# cpu.net
KiCad netlist of a schematic drawn in Altium Designer
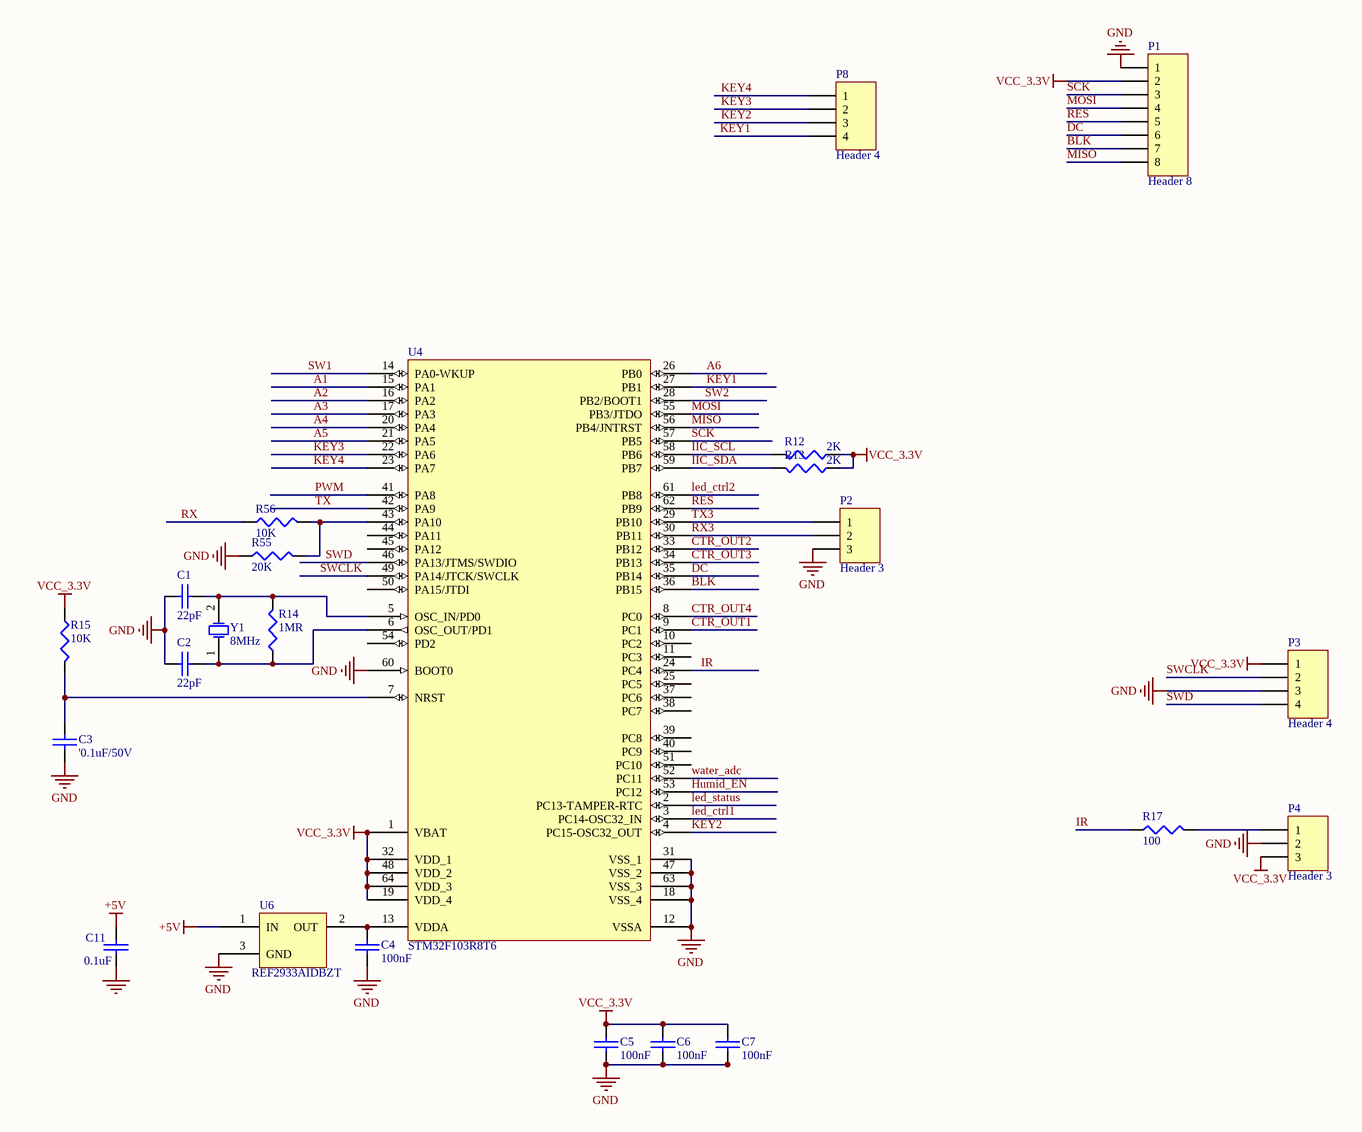
[diagram p0: cpu.SchDoc]

(export (version "E")
  (design (tool "Eeschema 10.0.6"))
  (components
    (comp (ref "C1")
      (value "22pF")
      (footprint "0805c")
      (description "Capacitor")
      (libsource (lib "SM") (part "CAP"))
    )
    (comp (ref "C2")
      (value "22pF")
      (footprint "0805c")
      (description "Capacitor")
      (libsource (lib "SM") (part "CAP"))
    )
    (comp (ref "C3")
      (value "'0.1uF/50V")
      (footprint "0805c")
      (description "Capacitor")
      (libsource (lib "SM") (part "CAP"))
    )
    (comp (ref "C4")
      (value "100nF")
      (footprint "0805c")
      (description "Capacitor")
      (libsource (lib "SM") (part "CAP"))
    )
    (comp (ref "C5")
      (value "100nF")
      (footprint "0805c")
      (description "Capacitor")
      (libsource (lib "SM") (part "CAP"))
    )
    (comp (ref "C6")
      (value "100nF")
      (footprint "0805c")
      (description "Capacitor")
      (libsource (lib "SM") (part "CAP"))
    )
    (comp (ref "C7")
      (value "100nF")
      (footprint "0805c")
      (description "Capacitor")
      (libsource (lib "SM") (part "CAP"))
    )
    (comp (ref "C11")
      (value "0.1uF")
      (footprint "0603C")
      (description "Capacitor")
      (libsource (lib "*") (part "CAP"))
    )
    (comp (ref "P1")
      (value "Header 8")
      (footprint "HDR1X8")
      (description "Header, 8-Pin")
      (fields (field (name "PUBLISHER") "Altium Limited"))
      (libsource (lib "Miscellaneous Connectors") (part "Header 8"))
    )
    (comp (ref "P2")
      (value "Header 3")
      (footprint "HDR1X3")
      (description "Header, 3-Pin")
      (fields (field (name "PUBLISHER") "Altium Limited"))
      (libsource (lib "Miscellaneous Connectors") (part "Header 3"))
    )
    (comp (ref "P3")
      (value "Header 4")
      (footprint "HDR1X4")
      (description "Header, 4-Pin")
      (fields (field (name "PUBLISHER") "Altium Limited"))
      (libsource (lib "Miscellaneous Connectors") (part "Header 4"))
    )
    (comp (ref "P4")
      (value "Header 3")
      (footprint "HDR1X3")
      (description "Header, 3-Pin")
      (fields (field (name "PUBLISHER") "Altium Limited"))
      (libsource (lib "Miscellaneous Connectors") (part "Header 3"))
    )
    (comp (ref "P8")
      (value "Header 4")
      (footprint "HDR1X4")
      (description "Header, 4-Pin")
      (fields (field (name "PUBLISHER") "Altium Limited"))
      (libsource (lib "Miscellaneous Connectors") (part "Header 4"))
    )
    (comp (ref "R12")
      (value "2K")
      (footprint "0805R")
      (description "Resistor")
      (fields (field (name "PUBLISHER") "Altium Limited"))
      (libsource (lib "SM") (part "Res3"))
    )
    (comp (ref "R13")
      (value "2K")
      (footprint "0805R")
      (description "Resistor")
      (fields (field (name "PUBLISHER") "Altium Limited"))
      (libsource (lib "SM") (part "Res3"))
    )
    (comp (ref "R14")
      (value "1MR")
      (footprint "0805R")
      (description "Resistor")
      (fields (field (name "PUBLISHER") "Altium Limited"))
      (libsource (lib "SM") (part "Res3"))
    )
    (comp (ref "R15")
      (value "10K")
      (footprint "0805R")
      (description "Resistor")
      (fields (field (name "PUBLISHER") "Altium Limited"))
      (libsource (lib "SM") (part "Res3"))
    )
    (comp (ref "R17")
      (value "100")
      (footprint "0603R")
      (description "Resistor")
      (fields (field (name "PUBLISHER") "Altium Limited"))
      (libsource (lib "SM") (part "Res3"))
    )
    (comp (ref "R55")
      (value "20K")
      (footprint "0603R")
      (description "Resistor")
      (fields (field (name "PUBLISHER") "Altium Limited"))
      (libsource (lib "SM") (part "Res3"))
    )
    (comp (ref "R56")
      (value "10K")
      (footprint "0805R")
      (description "Resistor")
      (fields (field (name "PUBLISHER") "Altium Limited"))
      (libsource (lib "SM") (part "Res3"))
    )
    (comp (ref "U4")
      (value "STM32F103R8T6")
      (footprint "LQFP-64")
      (description "STM32 ARM-based 32-bit MCU with 64 Kbytes Flash, 64-pin LQFP, Industrial Temperature")
      (fields (field (name "PUBLISHER") "Altium Limited"))
      (libsource (lib "ST Microcontroller 32-Bit STM32") (part "STM32F103R8T6"))
    )
    (comp (ref "U6")
      (value "REF2933AIDBZT")
      (footprint "SOT23-3")
      (libsource (lib "Schlib1") (part "REF3012"))
    )
    (comp (ref "Y1")
      (value "8MHz")
      (footprint "SMT5032")
      (description "Crystal Oscillator")
      (fields (field (name "PUBLISHER") "Altium Limited"))
      (libsource (lib "Miscellaneous Devices") (part "XTAL"))
    )
  )
  (nets
    (net (code "1") (name "+5V") (class "Default")
      (node (ref "C11") (pin "1") (pinfunction "1_1") (pintype "passive"))
      (node (ref "U6") (pin "1") (pinfunction "IN_1") (pintype "passive"))
    )
    (net (code "2") (name "/A1") (class "Default")
      (node (ref "U4") (pin "15") (pinfunction "PA1_15") (pintype "bidirectional"))
    )
    (net (code "3") (name "/A2") (class "Default")
      (node (ref "U4") (pin "16") (pinfunction "PA2_16") (pintype "bidirectional"))
    )
    (net (code "4") (name "/A3") (class "Default")
      (node (ref "U4") (pin "17") (pinfunction "PA3_17") (pintype "bidirectional"))
    )
    (net (code "5") (name "/A4") (class "Default")
      (node (ref "U4") (pin "20") (pinfunction "PA4_20") (pintype "bidirectional"))
    )
    (net (code "6") (name "/A5") (class "Default")
      (node (ref "U4") (pin "21") (pinfunction "PA5_21") (pintype "bidirectional"))
    )
    (net (code "7") (name "/A6") (class "Default")
      (node (ref "U4") (pin "26") (pinfunction "PB0_26") (pintype "bidirectional"))
    )
    (net (code "8") (name "/BLK") (class "Default")
      (node (ref "P1") (pin "7") (pinfunction "7_7") (pintype "passive"))
      (node (ref "U4") (pin "36") (pinfunction "PB15_36") (pintype "bidirectional"))
    )
    (net (code "9") (name "/CTR_OUT1") (class "Default")
      (node (ref "U4") (pin "9") (pinfunction "PC1_9") (pintype "bidirectional"))
    )
    (net (code "10") (name "/CTR_OUT2") (class "Default")
      (node (ref "U4") (pin "33") (pinfunction "PB12_33") (pintype "bidirectional"))
    )
    (net (code "11") (name "/CTR_OUT3") (class "Default")
      (node (ref "U4") (pin "34") (pinfunction "PB13_34") (pintype "bidirectional"))
    )
    (net (code "12") (name "/CTR_OUT4") (class "Default")
      (node (ref "U4") (pin "8") (pinfunction "PC0_8") (pintype "bidirectional"))
    )
    (net (code "13") (name "/DC") (class "Default")
      (node (ref "P1") (pin "6") (pinfunction "6_6") (pintype "passive"))
      (node (ref "U4") (pin "35") (pinfunction "PB14_35") (pintype "bidirectional"))
    )
    (net (code "14") (name "/Humid_EN") (class "Default")
      (node (ref "U4") (pin "53") (pinfunction "PC12_53") (pintype "bidirectional"))
    )
    (net (code "15") (name "/IIC_SCL") (class "Default")
      (node (ref "R12") (pin "2") (pinfunction "2_2") (pintype "passive"))
      (node (ref "U4") (pin "58") (pinfunction "PB6_58") (pintype "bidirectional"))
    )
    (net (code "16") (name "/IIC_SDA") (class "Default")
      (node (ref "R13") (pin "2") (pinfunction "2_2") (pintype "passive"))
      (node (ref "U4") (pin "59") (pinfunction "PB7_59") (pintype "bidirectional"))
    )
    (net (code "17") (name "/IR") (class "Default")
      (node (ref "R17") (pin "1") (pinfunction "1_1") (pintype "passive"))
      (node (ref "U4") (pin "24") (pinfunction "PC4_24") (pintype "bidirectional"))
    )
    (net (code "18") (name "/KEY1") (class "Default")
      (node (ref "P8") (pin "4") (pinfunction "4_4") (pintype "passive"))
      (node (ref "U4") (pin "27") (pinfunction "PB1_27") (pintype "bidirectional"))
    )
    (net (code "19") (name "/KEY2") (class "Default")
      (node (ref "P8") (pin "3") (pinfunction "3_3") (pintype "passive"))
      (node (ref "U4") (pin "4") (pinfunction "PC15-OSC32_OUT_4") (pintype "bidirectional"))
    )
    (net (code "20") (name "/KEY3") (class "Default")
      (node (ref "P8") (pin "2") (pinfunction "2_2") (pintype "passive"))
      (node (ref "U4") (pin "22") (pinfunction "PA6_22") (pintype "bidirectional"))
    )
    (net (code "21") (name "/KEY4") (class "Default")
      (node (ref "P8") (pin "1") (pinfunction "1_1") (pintype "passive"))
      (node (ref "U4") (pin "23") (pinfunction "PA7_23") (pintype "bidirectional"))
    )
    (net (code "22") (name "/MISO") (class "Default")
      (node (ref "P1") (pin "8") (pinfunction "8_8") (pintype "passive"))
      (node (ref "U4") (pin "56") (pinfunction "PB4/JNTRST_56") (pintype "bidirectional"))
    )
    (net (code "23") (name "/MOSI") (class "Default")
      (node (ref "P1") (pin "4") (pinfunction "4_4") (pintype "passive"))
      (node (ref "U4") (pin "55") (pinfunction "PB3/JTDO_55") (pintype "bidirectional"))
    )
    (net (code "24") (name "/PWM") (class "Default")
      (node (ref "U4") (pin "41") (pinfunction "PA8_41") (pintype "bidirectional"))
    )
    (net (code "25") (name "/RES") (class "Default")
      (node (ref "P1") (pin "5") (pinfunction "5_5") (pintype "passive"))
      (node (ref "U4") (pin "62") (pinfunction "PB9_62") (pintype "bidirectional"))
    )
    (net (code "26") (name "/RX") (class "Default")
      (node (ref "R56") (pin "1") (pinfunction "1_1") (pintype "passive"))
    )
    (net (code "27") (name "/RX3") (class "Default")
      (node (ref "P2") (pin "2") (pinfunction "2_2") (pintype "passive"))
      (node (ref "U4") (pin "30") (pinfunction "PB11_30") (pintype "bidirectional"))
    )
    (net (code "28") (name "/SCK") (class "Default")
      (node (ref "P1") (pin "3") (pinfunction "3_3") (pintype "passive"))
      (node (ref "U4") (pin "57") (pinfunction "PB5_57") (pintype "bidirectional"))
    )
    (net (code "29") (name "/SW1") (class "Default")
      (node (ref "U4") (pin "14") (pinfunction "PA0-WKUP_14") (pintype "bidirectional"))
    )
    (net (code "30") (name "/SW2") (class "Default")
      (node (ref "U4") (pin "28") (pinfunction "PB2/BOOT1_28") (pintype "bidirectional"))
    )
    (net (code "31") (name "/SWCLK") (class "Default")
      (node (ref "P3") (pin "2") (pinfunction "2_2") (pintype "passive"))
      (node (ref "U4") (pin "49") (pinfunction "PA14/JTCK/SWCLK_49") (pintype "bidirectional"))
    )
    (net (code "32") (name "/SWD") (class "Default")
      (node (ref "P3") (pin "4") (pinfunction "4_4") (pintype "passive"))
      (node (ref "U4") (pin "46") (pinfunction "PA13/JTMS/SWDIO_46") (pintype "bidirectional"))
    )
    (net (code "33") (name "/TX") (class "Default")
      (node (ref "U4") (pin "42") (pinfunction "PA9_42") (pintype "bidirectional"))
    )
    (net (code "34") (name "/TX3") (class "Default")
      (node (ref "P2") (pin "1") (pinfunction "1_1") (pintype "passive"))
      (node (ref "U4") (pin "29") (pinfunction "PB10_29") (pintype "bidirectional"))
    )
    (net (code "35") (name "/led_ctrl1") (class "Default")
      (node (ref "U4") (pin "3") (pinfunction "PC14-OSC32_IN_3") (pintype "bidirectional"))
    )
    (net (code "36") (name "/led_ctrl2") (class "Default")
      (node (ref "U4") (pin "61") (pinfunction "PB8_61") (pintype "bidirectional"))
    )
    (net (code "37") (name "/led_status") (class "Default")
      (node (ref "U4") (pin "2") (pinfunction "PC13-TAMPER-RTC_2") (pintype "bidirectional"))
    )
    (net (code "38") (name "/water_adc") (class "Default")
      (node (ref "U4") (pin "52") (pinfunction "PC11_52") (pintype "bidirectional"))
    )
    (net (code "39") (name "GND") (class "Default")
      (node (ref "C1") (pin "1") (pinfunction "1_1") (pintype "passive"))
      (node (ref "C11") (pin "2") (pinfunction "2_2") (pintype "passive"))
      (node (ref "C2") (pin "1") (pinfunction "1_1") (pintype "passive"))
      (node (ref "C3") (pin "1") (pinfunction "1_1") (pintype "passive"))
      (node (ref "C4") (pin "1") (pinfunction "1_1") (pintype "passive"))
      (node (ref "C5") (pin "1") (pinfunction "1_1") (pintype "passive"))
      (node (ref "C6") (pin "1") (pinfunction "1_1") (pintype "passive"))
      (node (ref "C7") (pin "1") (pinfunction "1_1") (pintype "passive"))
      (node (ref "P1") (pin "1") (pinfunction "1_1") (pintype "passive"))
      (node (ref "P2") (pin "3") (pinfunction "3_3") (pintype "passive"))
      (node (ref "P3") (pin "3") (pinfunction "3_3") (pintype "passive"))
      (node (ref "P4") (pin "2") (pinfunction "2_2") (pintype "passive"))
      (node (ref "R55") (pin "1") (pinfunction "1_1") (pintype "passive"))
      (node (ref "U4") (pin "12") (pinfunction "VSSA_12") (pintype "power_in"))
      (node (ref "U4") (pin "18") (pinfunction "VSS_4_18") (pintype "power_in"))
      (node (ref "U4") (pin "31") (pinfunction "VSS_1_31") (pintype "power_in"))
      (node (ref "U4") (pin "47") (pinfunction "VSS_2_47") (pintype "power_in"))
      (node (ref "U4") (pin "60") (pinfunction "BOOT0_60") (pintype "input"))
      (node (ref "U4") (pin "63") (pinfunction "VSS_3_63") (pintype "power_in"))
      (node (ref "U6") (pin "3") (pinfunction "GND_3") (pintype "passive"))
    )
    (net (code "40") (name "Net-(P4-Pad1)") (class "Default")
      (node (ref "P4") (pin "1") (pinfunction "1_1") (pintype "passive"))
      (node (ref "R17") (pin "2") (pinfunction "2_2") (pintype "passive"))
    )
    (net (code "41") (name "Net-(U4-NRST)") (class "Default")
      (node (ref "C3") (pin "2") (pinfunction "2_2") (pintype "passive"))
      (node (ref "R15") (pin "2") (pinfunction "2_2") (pintype "passive"))
      (node (ref "U4") (pin "7") (pinfunction "NRST_7") (pintype "bidirectional"))
    )
    (net (code "42") (name "Net-(U4-OSC_IN{slash}PD0)") (class "Default")
      (node (ref "C1") (pin "2") (pinfunction "2_2") (pintype "passive"))
      (node (ref "R14") (pin "2") (pinfunction "2_2") (pintype "passive"))
      (node (ref "U4") (pin "5") (pinfunction "OSC_IN/PD0_5") (pintype "input"))
      (node (ref "Y1") (pin "2") (pinfunction "OSC2_2") (pintype "passive"))
    )
    (net (code "43") (name "Net-(U4-OSC_OUT{slash}PD1)") (class "Default")
      (node (ref "C2") (pin "2") (pinfunction "2_2") (pintype "passive"))
      (node (ref "R14") (pin "1") (pinfunction "1_1") (pintype "passive"))
      (node (ref "U4") (pin "6") (pinfunction "OSC_OUT/PD1_6") (pintype "output"))
      (node (ref "Y1") (pin "1") (pinfunction "OSC1_1") (pintype "passive"))
    )
    (net (code "44") (name "Net-(U4-PA10)") (class "Default")
      (node (ref "R55") (pin "2") (pinfunction "2_2") (pintype "passive"))
      (node (ref "R56") (pin "2") (pinfunction "2_2") (pintype "passive"))
      (node (ref "U4") (pin "43") (pinfunction "PA10_43") (pintype "bidirectional"))
    )
    (net (code "45") (name "Net-(U4-VDDA)") (class "Default")
      (node (ref "C4") (pin "2") (pinfunction "2_2") (pintype "passive"))
      (node (ref "U4") (pin "13") (pinfunction "VDDA_13") (pintype "power_in"))
      (node (ref "U6") (pin "2") (pinfunction "OUT_2") (pintype "passive"))
    )
    (net (code "46") (name "VCC_3.3V") (class "Default")
      (node (ref "C5") (pin "2") (pinfunction "2_2") (pintype "passive"))
      (node (ref "C6") (pin "2") (pinfunction "2_2") (pintype "passive"))
      (node (ref "C7") (pin "2") (pinfunction "2_2") (pintype "passive"))
      (node (ref "P1") (pin "2") (pinfunction "2_2") (pintype "passive"))
      (node (ref "P3") (pin "1") (pinfunction "1_1") (pintype "passive"))
      (node (ref "P4") (pin "3") (pinfunction "3_3") (pintype "passive"))
      (node (ref "R12") (pin "1") (pinfunction "1_1") (pintype "passive"))
      (node (ref "R13") (pin "1") (pinfunction "1_1") (pintype "passive"))
      (node (ref "R15") (pin "1") (pinfunction "1_1") (pintype "passive"))
      (node (ref "U4") (pin "1") (pinfunction "VBAT_1") (pintype "power_in"))
      (node (ref "U4") (pin "19") (pinfunction "VDD_4_19") (pintype "power_in"))
      (node (ref "U4") (pin "32") (pinfunction "VDD_1_32") (pintype "power_in"))
      (node (ref "U4") (pin "48") (pinfunction "VDD_2_48") (pintype "power_in"))
      (node (ref "U4") (pin "64") (pinfunction "VDD_3_64") (pintype "power_in"))
    )
    (net (code "47") (name "unconnected-(U4-PA11-Pad44)") (class "Default")
      (node (ref "U4") (pin "44") (pinfunction "PA11_44") (pintype "bidirectional"))
    )
    (net (code "48") (name "unconnected-(U4-PA12-Pad45)") (class "Default")
      (node (ref "U4") (pin "45") (pinfunction "PA12_45") (pintype "bidirectional"))
    )
    (net (code "49") (name "unconnected-(U4-PA15{slash}JTDI-Pad50)") (class "Default")
      (node (ref "U4") (pin "50") (pinfunction "PA15/JTDI_50") (pintype "bidirectional"))
    )
    (net (code "50") (name "unconnected-(U4-PC2-Pad10)") (class "Default")
      (node (ref "U4") (pin "10") (pinfunction "PC2_10") (pintype "bidirectional"))
    )
    (net (code "51") (name "unconnected-(U4-PC3-Pad11)") (class "Default")
      (node (ref "U4") (pin "11") (pinfunction "PC3_11") (pintype "bidirectional"))
    )
    (net (code "52") (name "unconnected-(U4-PC5-Pad25)") (class "Default")
      (node (ref "U4") (pin "25") (pinfunction "PC5_25") (pintype "bidirectional"))
    )
    (net (code "53") (name "unconnected-(U4-PC6-Pad37)") (class "Default")
      (node (ref "U4") (pin "37") (pinfunction "PC6_37") (pintype "bidirectional"))
    )
    (net (code "54") (name "unconnected-(U4-PC7-Pad38)") (class "Default")
      (node (ref "U4") (pin "38") (pinfunction "PC7_38") (pintype "bidirectional"))
    )
    (net (code "55") (name "unconnected-(U4-PC8-Pad39)") (class "Default")
      (node (ref "U4") (pin "39") (pinfunction "PC8_39") (pintype "bidirectional"))
    )
    (net (code "56") (name "unconnected-(U4-PC9-Pad40)") (class "Default")
      (node (ref "U4") (pin "40") (pinfunction "PC9_40") (pintype "bidirectional"))
    )
    (net (code "57") (name "unconnected-(U4-PC10-Pad51)") (class "Default")
      (node (ref "U4") (pin "51") (pinfunction "PC10_51") (pintype "bidirectional"))
    )
    (net (code "58") (name "unconnected-(U4-PD2-Pad54)") (class "Default")
      (node (ref "U4") (pin "54") (pinfunction "PD2_54") (pintype "bidirectional"))
    )
  )
)
